# SCH_YY.net
KiCad netlist of a schematic drawn in EasyEDA
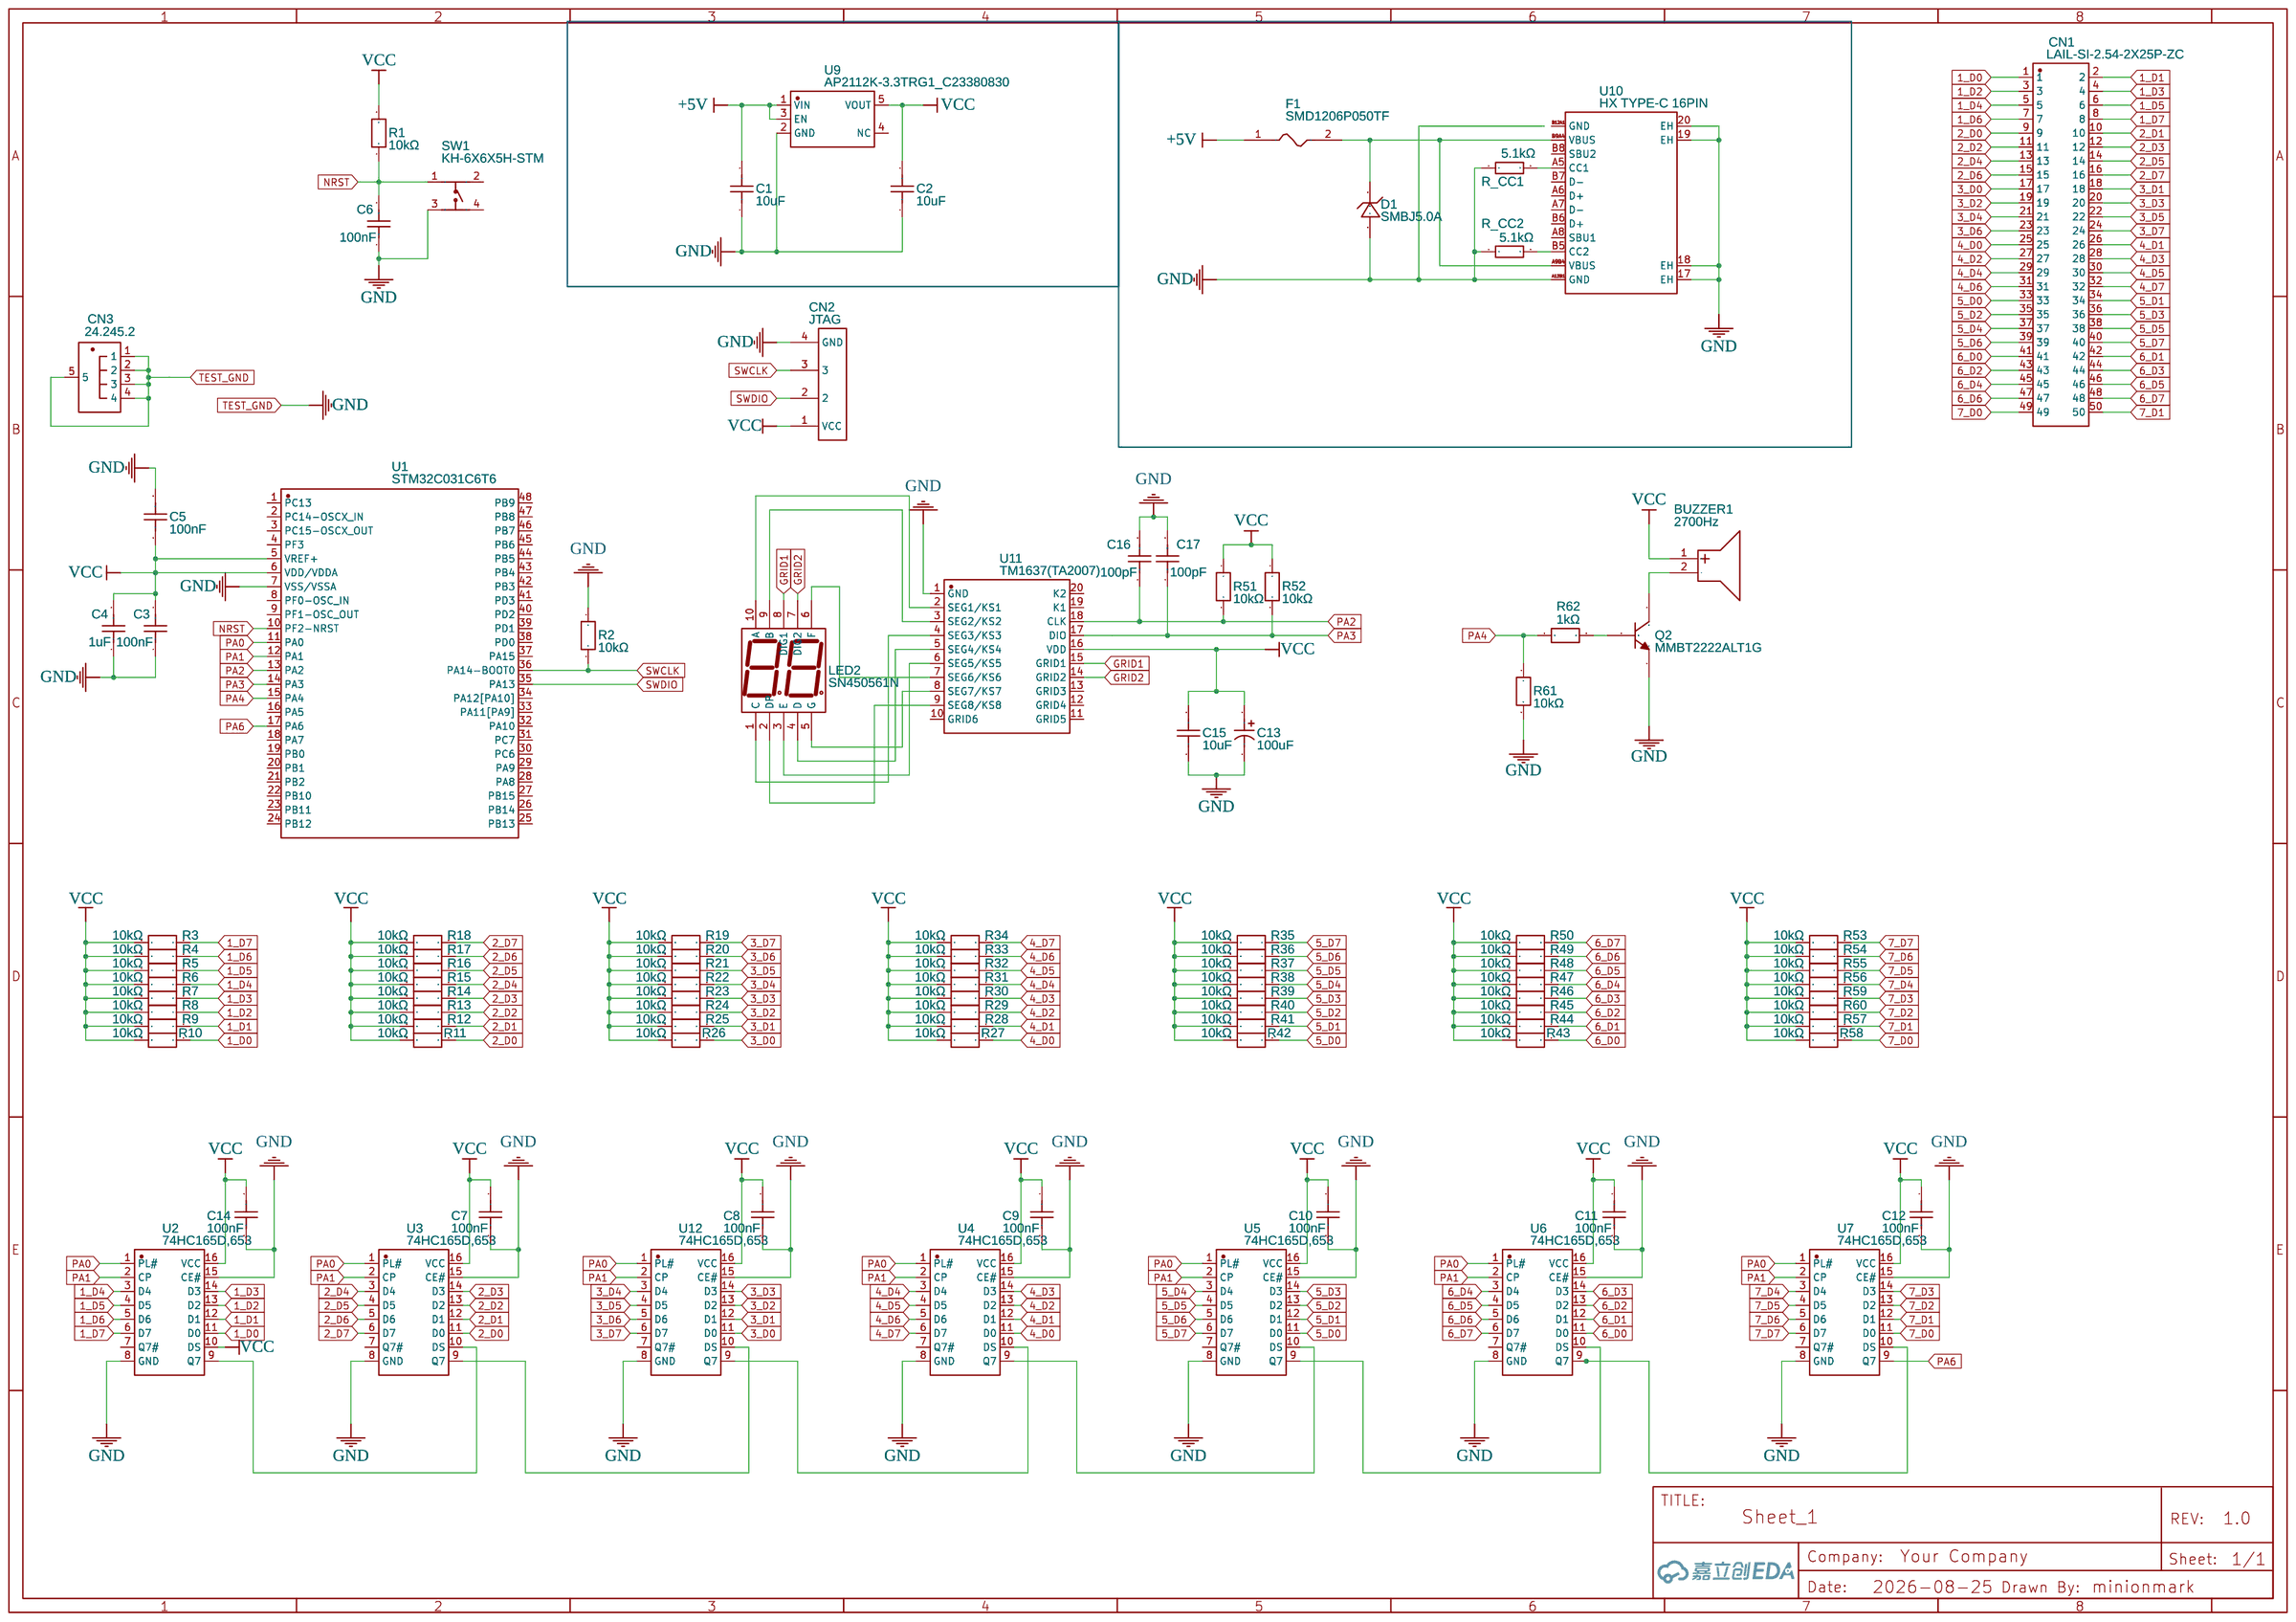
[diagram p0: schematic sheet]

(export (version "E")
  (design (tool "Eeschema 10.0.6"))
  (components
    (comp (ref "BUZZER1")
      (value "2700Hz")
      (fields
        (field (name "Manufacturer Part") "GSD9605YB-3V2800")
        (field (name "Manufacturer") "INGHAi(赢海)")
      )
      (libsource (lib "") (part "GSD9605YB-3V2800"))
    )
    (comp (ref "C1")
      (value "10uF")
      (fields
        (field (name "Manufacturer Part") "FCC0603X106K100CT")
        (field (name "Manufacturer") "FOJAN(富捷)")
      )
      (libsource (lib "") (part "FCC0603X106K100CT"))
    )
    (comp (ref "C2")
      (value "10uF")
      (fields
        (field (name "Manufacturer Part") "FCC0603X106K100CT")
        (field (name "Manufacturer") "FOJAN(富捷)")
      )
      (libsource (lib "") (part "FCC0603X106K100CT"))
    )
    (comp (ref "C3")
      (value "100nF")
      (fields (field (name "Manufacturer Part") "0603ZD104KAT2A") (field (name "Manufacturer") "Kyocera AVX"))
      (libsource (lib "") (part "0603ZD104KAT2A"))
    )
    (comp (ref "C4")
      (value "1uF")
      (fields (field (name "Manufacturer Part") "0603X105K100NT") (field (name "Manufacturer") "FH(风华)"))
      (libsource (lib "") (part "0603X105K100NT"))
    )
    (comp (ref "C5")
      (value "100nF")
      (fields (field (name "Manufacturer Part") "0603ZD104KAT2A") (field (name "Manufacturer") "Kyocera AVX"))
      (libsource (lib "") (part "0603ZD104KAT2A"))
    )
    (comp (ref "C6")
      (value "100nF")
      (fields (field (name "Manufacturer Part") "0603ZD104KAT2A") (field (name "Manufacturer") "Kyocera AVX"))
      (libsource (lib "") (part "0603ZD104KAT2A"))
    )
    (comp (ref "C7")
      (value "100nF")
      (fields (field (name "Manufacturer Part") "0603ZD104KAT2A") (field (name "Manufacturer") "Kyocera AVX"))
      (libsource (lib "") (part "0603ZD104KAT2A_1"))
    )
    (comp (ref "C8")
      (value "100nF")
      (fields (field (name "Manufacturer Part") "0603ZD104KAT2A") (field (name "Manufacturer") "Kyocera AVX"))
      (libsource (lib "") (part "0603ZD104KAT2A_1"))
    )
    (comp (ref "C9")
      (value "100nF")
      (fields (field (name "Manufacturer Part") "0603ZD104KAT2A") (field (name "Manufacturer") "Kyocera AVX"))
      (libsource (lib "") (part "0603ZD104KAT2A_1"))
    )
    (comp (ref "C10")
      (value "100nF")
      (fields (field (name "Manufacturer Part") "0603ZD104KAT2A") (field (name "Manufacturer") "Kyocera AVX"))
      (libsource (lib "") (part "0603ZD104KAT2A_1"))
    )
    (comp (ref "C11")
      (value "100nF")
      (fields (field (name "Manufacturer Part") "0603ZD104KAT2A") (field (name "Manufacturer") "Kyocera AVX"))
      (libsource (lib "") (part "0603ZD104KAT2A_1"))
    )
    (comp (ref "C12")
      (value "100nF")
      (fields (field (name "Manufacturer Part") "0603ZD104KAT2A") (field (name "Manufacturer") "Kyocera AVX"))
      (libsource (lib "") (part "0603ZD104KAT2A_1"))
    )
    (comp (ref "C13")
      (value "100uF")
      (fields (field (name "Manufacturer Part") "JVJ25V100M6x5") (field (name "Manufacturer") "JIERR(捷而瑞)"))
      (libsource (lib "") (part "JVJ25V100M6X5"))
    )
    (comp (ref "C14")
      (value "100nF")
      (fields (field (name "Manufacturer Part") "0603ZD104KAT2A") (field (name "Manufacturer") "Kyocera AVX"))
      (libsource (lib "") (part "0603ZD104KAT2A_1"))
    )
    (comp (ref "C15")
      (value "10uF")
      (fields
        (field (name "Manufacturer Part") "FCC0603X106K100CT")
        (field (name "Manufacturer") "FOJAN(富捷)")
      )
      (libsource (lib "") (part "FCC0603X106K100CT"))
    )
    (comp (ref "C16")
      (value "100pF")
      (fields
        (field (name "Manufacturer Part") "CC0603JRNPO9BN101")
        (field (name "Manufacturer") "YAGEO(国巨)")
      )
      (libsource (lib "") (part "CC0603JRNPO9BN101"))
    )
    (comp (ref "C17")
      (value "100pF")
      (fields
        (field (name "Manufacturer Part") "CC0603JRNPO9BN101")
        (field (name "Manufacturer") "YAGEO(国巨)")
      )
      (libsource (lib "") (part "CC0603JRNPO9BN101"))
    )
    (comp (ref "CN1")
      (value "LAIL-SI-2.54-2X25P-ZC")
      (fields (field (name "Manufacturer") "莱联"))
      (libsource (lib "") (part "LAIL-SI-2.54-2X25P-ZC"))
    )
    (comp (ref "CN2") (value "JTAG") (libsource (lib "") (part "JTAG")))
    (comp (ref "CN3")
      (value "24.245.2")
      (fields (field (name "Manufacturer") "AMASS(艾迈斯)"))
      (libsource (lib "") (part "24.245.2"))
    )
    (comp (ref "D1")
      (value "SMBJ5.0A")
      (fields (field (name "Manufacturer") "MDD(辰达半导体)"))
      (libsource (lib "") (part "SMBJ5.0A-C113974"))
    )
    (comp (ref "F1")
      (value "SMD1206P050TF")
      (fields (field (name "Manufacturer") "RUILON(瑞隆源)"))
      (libsource (lib "") (part "SMD1206P050TF"))
    )
    (comp (ref "LED2")
      (value "SN450561N")
      (fields (field (name "Manufacturer") "ARKLED(方舟)"))
      (libsource (lib "") (part "SN450561N"))
    )
    (comp (ref "Q2")
      (value "MMBT2222ALT1G")
      (fields (field (name "Manufacturer") "onsemi(安森美)"))
      (libsource (lib "") (part "MMBT2222ALT1G"))
    )
    (comp (ref "R1")
      (value "10kΩ")
      (fields (field (name "Manufacturer Part") "FRC0603J103 TS") (field (name "Manufacturer") "FOJAN(富捷)"))
      (libsource (lib "") (part "FRC0603J103TS_2"))
    )
    (comp (ref "R2")
      (value "10kΩ")
      (fields (field (name "Manufacturer Part") "FRC0603J103 TS") (field (name "Manufacturer") "FOJAN(富捷)"))
      (libsource (lib "") (part "FRC0603J103TS_1"))
    )
    (comp (ref "R3")
      (value "10kΩ")
      (fields (field (name "Manufacturer Part") "FRC0603J103 TS") (field (name "Manufacturer") "FOJAN(富捷)"))
      (libsource (lib "") (part "FRC0603J103TS"))
    )
    (comp (ref "R4")
      (value "10kΩ")
      (fields (field (name "Manufacturer Part") "FRC0603J103 TS") (field (name "Manufacturer") "FOJAN(富捷)"))
      (libsource (lib "") (part "FRC0603J103TS"))
    )
    (comp (ref "R5")
      (value "10kΩ")
      (fields (field (name "Manufacturer Part") "FRC0603J103 TS") (field (name "Manufacturer") "FOJAN(富捷)"))
      (libsource (lib "") (part "FRC0603J103TS"))
    )
    (comp (ref "R6")
      (value "10kΩ")
      (fields (field (name "Manufacturer Part") "FRC0603J103 TS") (field (name "Manufacturer") "FOJAN(富捷)"))
      (libsource (lib "") (part "FRC0603J103TS"))
    )
    (comp (ref "R7")
      (value "10kΩ")
      (fields (field (name "Manufacturer Part") "FRC0603J103 TS") (field (name "Manufacturer") "FOJAN(富捷)"))
      (libsource (lib "") (part "FRC0603J103TS"))
    )
    (comp (ref "R8")
      (value "10kΩ")
      (fields (field (name "Manufacturer Part") "FRC0603J103 TS") (field (name "Manufacturer") "FOJAN(富捷)"))
      (libsource (lib "") (part "FRC0603J103TS"))
    )
    (comp (ref "R9")
      (value "10kΩ")
      (fields (field (name "Manufacturer Part") "FRC0603J103 TS") (field (name "Manufacturer") "FOJAN(富捷)"))
      (libsource (lib "") (part "FRC0603J103TS"))
    )
    (comp (ref "R10")
      (value "10kΩ")
      (fields (field (name "Manufacturer Part") "FRC0603J103 TS") (field (name "Manufacturer") "FOJAN(富捷)"))
      (libsource (lib "") (part "FRC0603J103TS"))
    )
    (comp (ref "R11")
      (value "10kΩ")
      (fields (field (name "Manufacturer Part") "FRC0603J103 TS") (field (name "Manufacturer") "FOJAN(富捷)"))
      (libsource (lib "") (part "FRC0603J103TS"))
    )
    (comp (ref "R12")
      (value "10kΩ")
      (fields (field (name "Manufacturer Part") "FRC0603J103 TS") (field (name "Manufacturer") "FOJAN(富捷)"))
      (libsource (lib "") (part "FRC0603J103TS"))
    )
    (comp (ref "R13")
      (value "10kΩ")
      (fields (field (name "Manufacturer Part") "FRC0603J103 TS") (field (name "Manufacturer") "FOJAN(富捷)"))
      (libsource (lib "") (part "FRC0603J103TS"))
    )
    (comp (ref "R14")
      (value "10kΩ")
      (fields (field (name "Manufacturer Part") "FRC0603J103 TS") (field (name "Manufacturer") "FOJAN(富捷)"))
      (libsource (lib "") (part "FRC0603J103TS"))
    )
    (comp (ref "R15")
      (value "10kΩ")
      (fields (field (name "Manufacturer Part") "FRC0603J103 TS") (field (name "Manufacturer") "FOJAN(富捷)"))
      (libsource (lib "") (part "FRC0603J103TS"))
    )
    (comp (ref "R16")
      (value "10kΩ")
      (fields (field (name "Manufacturer Part") "FRC0603J103 TS") (field (name "Manufacturer") "FOJAN(富捷)"))
      (libsource (lib "") (part "FRC0603J103TS"))
    )
    (comp (ref "R17")
      (value "10kΩ")
      (fields (field (name "Manufacturer Part") "FRC0603J103 TS") (field (name "Manufacturer") "FOJAN(富捷)"))
      (libsource (lib "") (part "FRC0603J103TS"))
    )
    (comp (ref "R18")
      (value "10kΩ")
      (fields (field (name "Manufacturer Part") "FRC0603J103 TS") (field (name "Manufacturer") "FOJAN(富捷)"))
      (libsource (lib "") (part "FRC0603J103TS"))
    )
    (comp (ref "R19")
      (value "10kΩ")
      (fields (field (name "Manufacturer Part") "FRC0603J103 TS") (field (name "Manufacturer") "FOJAN(富捷)"))
      (libsource (lib "") (part "FRC0603J103TS"))
    )
    (comp (ref "R20")
      (value "10kΩ")
      (fields (field (name "Manufacturer Part") "FRC0603J103 TS") (field (name "Manufacturer") "FOJAN(富捷)"))
      (libsource (lib "") (part "FRC0603J103TS"))
    )
    (comp (ref "R21")
      (value "10kΩ")
      (fields (field (name "Manufacturer Part") "FRC0603J103 TS") (field (name "Manufacturer") "FOJAN(富捷)"))
      (libsource (lib "") (part "FRC0603J103TS"))
    )
    (comp (ref "R22")
      (value "10kΩ")
      (fields (field (name "Manufacturer Part") "FRC0603J103 TS") (field (name "Manufacturer") "FOJAN(富捷)"))
      (libsource (lib "") (part "FRC0603J103TS"))
    )
    (comp (ref "R23")
      (value "10kΩ")
      (fields (field (name "Manufacturer Part") "FRC0603J103 TS") (field (name "Manufacturer") "FOJAN(富捷)"))
      (libsource (lib "") (part "FRC0603J103TS"))
    )
    (comp (ref "R24")
      (value "10kΩ")
      (fields (field (name "Manufacturer Part") "FRC0603J103 TS") (field (name "Manufacturer") "FOJAN(富捷)"))
      (libsource (lib "") (part "FRC0603J103TS"))
    )
    (comp (ref "R25")
      (value "10kΩ")
      (fields (field (name "Manufacturer Part") "FRC0603J103 TS") (field (name "Manufacturer") "FOJAN(富捷)"))
      (libsource (lib "") (part "FRC0603J103TS"))
    )
    (comp (ref "R26")
      (value "10kΩ")
      (fields (field (name "Manufacturer Part") "FRC0603J103 TS") (field (name "Manufacturer") "FOJAN(富捷)"))
      (libsource (lib "") (part "FRC0603J103TS"))
    )
    (comp (ref "R27")
      (value "10kΩ")
      (fields (field (name "Manufacturer Part") "FRC0603J103 TS") (field (name "Manufacturer") "FOJAN(富捷)"))
      (libsource (lib "") (part "FRC0603J103TS"))
    )
    (comp (ref "R28")
      (value "10kΩ")
      (fields (field (name "Manufacturer Part") "FRC0603J103 TS") (field (name "Manufacturer") "FOJAN(富捷)"))
      (libsource (lib "") (part "FRC0603J103TS"))
    )
    (comp (ref "R29")
      (value "10kΩ")
      (fields (field (name "Manufacturer Part") "FRC0603J103 TS") (field (name "Manufacturer") "FOJAN(富捷)"))
      (libsource (lib "") (part "FRC0603J103TS"))
    )
    (comp (ref "R30")
      (value "10kΩ")
      (fields (field (name "Manufacturer Part") "FRC0603J103 TS") (field (name "Manufacturer") "FOJAN(富捷)"))
      (libsource (lib "") (part "FRC0603J103TS"))
    )
    (comp (ref "R31")
      (value "10kΩ")
      (fields (field (name "Manufacturer Part") "FRC0603J103 TS") (field (name "Manufacturer") "FOJAN(富捷)"))
      (libsource (lib "") (part "FRC0603J103TS"))
    )
    (comp (ref "R32")
      (value "10kΩ")
      (fields (field (name "Manufacturer Part") "FRC0603J103 TS") (field (name "Manufacturer") "FOJAN(富捷)"))
      (libsource (lib "") (part "FRC0603J103TS"))
    )
    (comp (ref "R33")
      (value "10kΩ")
      (fields (field (name "Manufacturer Part") "FRC0603J103 TS") (field (name "Manufacturer") "FOJAN(富捷)"))
      (libsource (lib "") (part "FRC0603J103TS"))
    )
    (comp (ref "R34")
      (value "10kΩ")
      (fields (field (name "Manufacturer Part") "FRC0603J103 TS") (field (name "Manufacturer") "FOJAN(富捷)"))
      (libsource (lib "") (part "FRC0603J103TS"))
    )
    (comp (ref "R35")
      (value "10kΩ")
      (fields (field (name "Manufacturer Part") "FRC0603J103 TS") (field (name "Manufacturer") "FOJAN(富捷)"))
      (libsource (lib "") (part "FRC0603J103TS"))
    )
    (comp (ref "R36")
      (value "10kΩ")
      (fields (field (name "Manufacturer Part") "FRC0603J103 TS") (field (name "Manufacturer") "FOJAN(富捷)"))
      (libsource (lib "") (part "FRC0603J103TS"))
    )
    (comp (ref "R37")
      (value "10kΩ")
      (fields (field (name "Manufacturer Part") "FRC0603J103 TS") (field (name "Manufacturer") "FOJAN(富捷)"))
      (libsource (lib "") (part "FRC0603J103TS"))
    )
    (comp (ref "R38")
      (value "10kΩ")
      (fields (field (name "Manufacturer Part") "FRC0603J103 TS") (field (name "Manufacturer") "FOJAN(富捷)"))
      (libsource (lib "") (part "FRC0603J103TS"))
    )
    (comp (ref "R39")
      (value "10kΩ")
      (fields (field (name "Manufacturer Part") "FRC0603J103 TS") (field (name "Manufacturer") "FOJAN(富捷)"))
      (libsource (lib "") (part "FRC0603J103TS"))
    )
    (comp (ref "R40")
      (value "10kΩ")
      (fields (field (name "Manufacturer Part") "FRC0603J103 TS") (field (name "Manufacturer") "FOJAN(富捷)"))
      (libsource (lib "") (part "FRC0603J103TS"))
    )
    (comp (ref "R41")
      (value "10kΩ")
      (fields (field (name "Manufacturer Part") "FRC0603J103 TS") (field (name "Manufacturer") "FOJAN(富捷)"))
      (libsource (lib "") (part "FRC0603J103TS"))
    )
    (comp (ref "R42")
      (value "10kΩ")
      (fields (field (name "Manufacturer Part") "FRC0603J103 TS") (field (name "Manufacturer") "FOJAN(富捷)"))
      (libsource (lib "") (part "FRC0603J103TS"))
    )
    (comp (ref "R43")
      (value "10kΩ")
      (fields (field (name "Manufacturer Part") "FRC0603J103 TS") (field (name "Manufacturer") "FOJAN(富捷)"))
      (libsource (lib "") (part "FRC0603J103TS"))
    )
    (comp (ref "R44")
      (value "10kΩ")
      (fields (field (name "Manufacturer Part") "FRC0603J103 TS") (field (name "Manufacturer") "FOJAN(富捷)"))
      (libsource (lib "") (part "FRC0603J103TS"))
    )
    (comp (ref "R45")
      (value "10kΩ")
      (fields (field (name "Manufacturer Part") "FRC0603J103 TS") (field (name "Manufacturer") "FOJAN(富捷)"))
      (libsource (lib "") (part "FRC0603J103TS"))
    )
    (comp (ref "R46")
      (value "10kΩ")
      (fields (field (name "Manufacturer Part") "FRC0603J103 TS") (field (name "Manufacturer") "FOJAN(富捷)"))
      (libsource (lib "") (part "FRC0603J103TS"))
    )
    (comp (ref "R47")
      (value "10kΩ")
      (fields (field (name "Manufacturer Part") "FRC0603J103 TS") (field (name "Manufacturer") "FOJAN(富捷)"))
      (libsource (lib "") (part "FRC0603J103TS"))
    )
    (comp (ref "R48")
      (value "10kΩ")
      (fields (field (name "Manufacturer Part") "FRC0603J103 TS") (field (name "Manufacturer") "FOJAN(富捷)"))
      (libsource (lib "") (part "FRC0603J103TS"))
    )
    (comp (ref "R49")
      (value "10kΩ")
      (fields (field (name "Manufacturer Part") "FRC0603J103 TS") (field (name "Manufacturer") "FOJAN(富捷)"))
      (libsource (lib "") (part "FRC0603J103TS"))
    )
    (comp (ref "R50")
      (value "10kΩ")
      (fields (field (name "Manufacturer Part") "FRC0603J103 TS") (field (name "Manufacturer") "FOJAN(富捷)"))
      (libsource (lib "") (part "FRC0603J103TS"))
    )
    (comp (ref "R51")
      (value "10kΩ")
      (fields (field (name "Manufacturer Part") "FRC0603J103 TS") (field (name "Manufacturer") "FOJAN(富捷)"))
      (libsource (lib "") (part "FRC0603J103TS_1"))
    )
    (comp (ref "R52")
      (value "10kΩ")
      (fields (field (name "Manufacturer Part") "FRC0603J103 TS") (field (name "Manufacturer") "FOJAN(富捷)"))
      (libsource (lib "") (part "FRC0603J103TS_1"))
    )
    (comp (ref "R53")
      (value "10kΩ")
      (fields (field (name "Manufacturer Part") "FRC0603J103 TS") (field (name "Manufacturer") "FOJAN(富捷)"))
      (libsource (lib "") (part "FRC0603J103TS"))
    )
    (comp (ref "R54")
      (value "10kΩ")
      (fields (field (name "Manufacturer Part") "FRC0603J103 TS") (field (name "Manufacturer") "FOJAN(富捷)"))
      (libsource (lib "") (part "FRC0603J103TS"))
    )
    (comp (ref "R55")
      (value "10kΩ")
      (fields (field (name "Manufacturer Part") "FRC0603J103 TS") (field (name "Manufacturer") "FOJAN(富捷)"))
      (libsource (lib "") (part "FRC0603J103TS"))
    )
    (comp (ref "R56")
      (value "10kΩ")
      (fields (field (name "Manufacturer Part") "FRC0603J103 TS") (field (name "Manufacturer") "FOJAN(富捷)"))
      (libsource (lib "") (part "FRC0603J103TS"))
    )
    (comp (ref "R57")
      (value "10kΩ")
      (fields (field (name "Manufacturer Part") "FRC0603J103 TS") (field (name "Manufacturer") "FOJAN(富捷)"))
      (libsource (lib "") (part "FRC0603J103TS"))
    )
    (comp (ref "R58")
      (value "10kΩ")
      (fields (field (name "Manufacturer Part") "FRC0603J103 TS") (field (name "Manufacturer") "FOJAN(富捷)"))
      (libsource (lib "") (part "FRC0603J103TS"))
    )
    (comp (ref "R59")
      (value "10kΩ")
      (fields (field (name "Manufacturer Part") "FRC0603J103 TS") (field (name "Manufacturer") "FOJAN(富捷)"))
      (libsource (lib "") (part "FRC0603J103TS"))
    )
    (comp (ref "R60")
      (value "10kΩ")
      (fields (field (name "Manufacturer Part") "FRC0603J103 TS") (field (name "Manufacturer") "FOJAN(富捷)"))
      (libsource (lib "") (part "FRC0603J103TS"))
    )
    (comp (ref "R61")
      (value "10kΩ")
      (fields (field (name "Manufacturer Part") "FRC0603J103 TS") (field (name "Manufacturer") "FOJAN(富捷)"))
      (libsource (lib "") (part "FRC0603J103TS_1"))
    )
    (comp (ref "R62")
      (value "1kΩ")
      (fields (field (name "Manufacturer Part") "FRC0603F1001TS") (field (name "Manufacturer") "FOJAN(富捷)"))
      (libsource (lib "") (part "FRC0603F1001TS"))
    )
    (comp (ref "R_CC1")
      (value "5.1kΩ")
      (fields (field (name "Manufacturer Part") "RT0603BRD075K1L") (field (name "Manufacturer") "YAGEO(国巨)"))
      (libsource (lib "") (part "RT0603BRD075K1L"))
    )
    (comp (ref "R_CC2")
      (value "5.1kΩ")
      (fields (field (name "Manufacturer Part") "RT0603BRD075K1L") (field (name "Manufacturer") "YAGEO(国巨)"))
      (libsource (lib "") (part "RT0603BRD075K1L"))
    )
    (comp (ref "SW1")
      (value "KH-6X6X5H-STM")
      (fields (field (name "Manufacturer") "kinghelm(金航标)"))
      (libsource (lib "") (part "KH-6X6X5H-STM"))
    )
    (comp (ref "U1")
      (value "STM32C031C6T6")
      (fields (field (name "Manufacturer") "ST(意法半导体)"))
      (libsource (lib "") (part "STM32C031C6T6"))
    )
    (comp (ref "U2")
      (value "74HC165D,653")
      (fields (field (name "Manufacturer") "Nexperia(安世)"))
      (libsource (lib "") (part "74HC165D,653"))
    )
    (comp (ref "U3")
      (value "74HC165D,653")
      (fields (field (name "Manufacturer") "Nexperia(安世)"))
      (libsource (lib "") (part "74HC165D,653"))
    )
    (comp (ref "U4")
      (value "74HC165D,653")
      (fields (field (name "Manufacturer") "Nexperia(安世)"))
      (libsource (lib "") (part "74HC165D,653"))
    )
    (comp (ref "U5")
      (value "74HC165D,653")
      (fields (field (name "Manufacturer") "Nexperia(安世)"))
      (libsource (lib "") (part "74HC165D,653"))
    )
    (comp (ref "U6")
      (value "74HC165D,653")
      (fields (field (name "Manufacturer") "Nexperia(安世)"))
      (libsource (lib "") (part "74HC165D,653"))
    )
    (comp (ref "U7")
      (value "74HC165D,653")
      (fields (field (name "Manufacturer") "Nexperia(安世)"))
      (libsource (lib "") (part "74HC165D,653"))
    )
    (comp (ref "U9")
      (value "AP2112K-3.3TRG1_C23380830")
      (fields
        (field (name "Manufacturer Part") "AP2112K-3.3TRG1")
        (field (name "Manufacturer") "TECH PUBLIC(台舟)")
      )
      (libsource (lib "") (part "AP2112K-3.3TRG1_C23380830"))
    )
    (comp (ref "U10")
      (value "HX TYPE-C 16PIN")
      (fields (field (name "Manufacturer") "hanxia(韩下)"))
      (libsource (lib "") (part "HX TYPE-C 16PIN"))
    )
    (comp (ref "U11")
      (value "TM1637(TA2007)")
      (fields (field (name "Manufacturer") "TM(天微)"))
      (libsource (lib "") (part "TM1637(TA2007)"))
    )
    (comp (ref "U12")
      (value "74HC165D,653")
      (fields (field (name "Manufacturer") "Nexperia(安世)"))
      (libsource (lib "") (part "74HC165D,653"))
    )
  )
  (nets
    (net (code "1") (name "+5V") (class "Default")
      (node (ref "C1") (pin "2") (pinfunction "2_2") (pintype "unspecified"))
      (node (ref "F1") (pin "1") (pinfunction "1_1") (pintype "unspecified"))
      (node (ref "U9") (pin "1") (pinfunction "VIN_1") (pintype "unspecified"))
      (node (ref "U9") (pin "3") (pinfunction "EN_3") (pintype "unspecified"))
    )
    (net (code "2") (name "1_D0") (class "Default")
      (node (ref "CN1") (pin "1") (pinfunction "1_1") (pintype "unspecified"))
      (node (ref "R10") (pin "1") (pinfunction "1_1") (pintype "unspecified"))
      (node (ref "U2") (pin "11") (pinfunction "D0_11") (pintype "unspecified"))
    )
    (net (code "3") (name "1_D1") (class "Default")
      (node (ref "CN1") (pin "2") (pinfunction "2_2") (pintype "unspecified"))
      (node (ref "R9") (pin "1") (pinfunction "1_1") (pintype "unspecified"))
      (node (ref "U2") (pin "12") (pinfunction "D1_12") (pintype "unspecified"))
    )
    (net (code "4") (name "1_D2") (class "Default")
      (node (ref "CN1") (pin "3") (pinfunction "3_3") (pintype "unspecified"))
      (node (ref "R8") (pin "1") (pinfunction "1_1") (pintype "unspecified"))
      (node (ref "U2") (pin "13") (pinfunction "D2_13") (pintype "unspecified"))
    )
    (net (code "5") (name "1_D3") (class "Default")
      (node (ref "CN1") (pin "4") (pinfunction "4_4") (pintype "unspecified"))
      (node (ref "R7") (pin "1") (pinfunction "1_1") (pintype "unspecified"))
      (node (ref "U2") (pin "14") (pinfunction "D3_14") (pintype "unspecified"))
    )
    (net (code "6") (name "1_D4") (class "Default")
      (node (ref "CN1") (pin "5") (pinfunction "5_5") (pintype "unspecified"))
      (node (ref "R6") (pin "1") (pinfunction "1_1") (pintype "unspecified"))
      (node (ref "U2") (pin "3") (pinfunction "D4_3") (pintype "unspecified"))
    )
    (net (code "7") (name "1_D5") (class "Default")
      (node (ref "CN1") (pin "6") (pinfunction "6_6") (pintype "unspecified"))
      (node (ref "R5") (pin "1") (pinfunction "1_1") (pintype "unspecified"))
      (node (ref "U2") (pin "4") (pinfunction "D5_4") (pintype "unspecified"))
    )
    (net (code "8") (name "1_D6") (class "Default")
      (node (ref "CN1") (pin "7") (pinfunction "7_7") (pintype "unspecified"))
      (node (ref "R4") (pin "1") (pinfunction "1_1") (pintype "unspecified"))
      (node (ref "U2") (pin "5") (pinfunction "D6_5") (pintype "unspecified"))
    )
    (net (code "9") (name "1_D7") (class "Default")
      (node (ref "CN1") (pin "8") (pinfunction "8_8") (pintype "unspecified"))
      (node (ref "R3") (pin "1") (pinfunction "1_1") (pintype "unspecified"))
      (node (ref "U2") (pin "6") (pinfunction "D7_6") (pintype "unspecified"))
    )
    (net (code "10") (name "2_D0") (class "Default")
      (node (ref "CN1") (pin "9") (pinfunction "9_9") (pintype "unspecified"))
      (node (ref "R11") (pin "1") (pinfunction "1_1") (pintype "unspecified"))
      (node (ref "U3") (pin "11") (pinfunction "D0_11") (pintype "unspecified"))
    )
    (net (code "11") (name "2_D1") (class "Default")
      (node (ref "CN1") (pin "10") (pinfunction "10_10") (pintype "unspecified"))
      (node (ref "R12") (pin "1") (pinfunction "1_1") (pintype "unspecified"))
      (node (ref "U3") (pin "12") (pinfunction "D1_12") (pintype "unspecified"))
    )
    (net (code "12") (name "2_D2") (class "Default")
      (node (ref "CN1") (pin "11") (pinfunction "11_11") (pintype "unspecified"))
      (node (ref "R13") (pin "1") (pinfunction "1_1") (pintype "unspecified"))
      (node (ref "U3") (pin "13") (pinfunction "D2_13") (pintype "unspecified"))
    )
    (net (code "13") (name "2_D3") (class "Default")
      (node (ref "CN1") (pin "12") (pinfunction "12_12") (pintype "unspecified"))
      (node (ref "R14") (pin "1") (pinfunction "1_1") (pintype "unspecified"))
      (node (ref "U3") (pin "14") (pinfunction "D3_14") (pintype "unspecified"))
    )
    (net (code "14") (name "2_D4") (class "Default")
      (node (ref "CN1") (pin "13") (pinfunction "13_13") (pintype "unspecified"))
      (node (ref "R15") (pin "1") (pinfunction "1_1") (pintype "unspecified"))
      (node (ref "U3") (pin "3") (pinfunction "D4_3") (pintype "unspecified"))
    )
    (net (code "15") (name "2_D5") (class "Default")
      (node (ref "CN1") (pin "14") (pinfunction "14_14") (pintype "unspecified"))
      (node (ref "R16") (pin "1") (pinfunction "1_1") (pintype "unspecified"))
      (node (ref "U3") (pin "4") (pinfunction "D5_4") (pintype "unspecified"))
    )
    (net (code "16") (name "2_D6") (class "Default")
      (node (ref "CN1") (pin "15") (pinfunction "15_15") (pintype "unspecified"))
      (node (ref "R17") (pin "1") (pinfunction "1_1") (pintype "unspecified"))
      (node (ref "U3") (pin "5") (pinfunction "D6_5") (pintype "unspecified"))
    )
    (net (code "17") (name "2_D7") (class "Default")
      (node (ref "CN1") (pin "16") (pinfunction "16_16") (pintype "unspecified"))
      (node (ref "R18") (pin "1") (pinfunction "1_1") (pintype "unspecified"))
      (node (ref "U3") (pin "6") (pinfunction "D7_6") (pintype "unspecified"))
    )
    (net (code "18") (name "3_D0") (class "Default")
      (node (ref "CN1") (pin "17") (pinfunction "17_17") (pintype "unspecified"))
      (node (ref "R26") (pin "1") (pinfunction "1_1") (pintype "unspecified"))
      (node (ref "U12") (pin "11") (pinfunction "D0_11") (pintype "unspecified"))
    )
    (net (code "19") (name "3_D1") (class "Default")
      (node (ref "CN1") (pin "18") (pinfunction "18_18") (pintype "unspecified"))
      (node (ref "R25") (pin "1") (pinfunction "1_1") (pintype "unspecified"))
      (node (ref "U12") (pin "12") (pinfunction "D1_12") (pintype "unspecified"))
    )
    (net (code "20") (name "3_D2") (class "Default")
      (node (ref "CN1") (pin "19") (pinfunction "19_19") (pintype "unspecified"))
      (node (ref "R24") (pin "1") (pinfunction "1_1") (pintype "unspecified"))
      (node (ref "U12") (pin "13") (pinfunction "D2_13") (pintype "unspecified"))
    )
    (net (code "21") (name "3_D3") (class "Default")
      (node (ref "CN1") (pin "20") (pinfunction "20_20") (pintype "unspecified"))
      (node (ref "R23") (pin "1") (pinfunction "1_1") (pintype "unspecified"))
      (node (ref "U12") (pin "14") (pinfunction "D3_14") (pintype "unspecified"))
    )
    (net (code "22") (name "3_D4") (class "Default")
      (node (ref "CN1") (pin "21") (pinfunction "21_21") (pintype "unspecified"))
      (node (ref "R22") (pin "1") (pinfunction "1_1") (pintype "unspecified"))
      (node (ref "U12") (pin "3") (pinfunction "D4_3") (pintype "unspecified"))
    )
    (net (code "23") (name "3_D5") (class "Default")
      (node (ref "CN1") (pin "22") (pinfunction "22_22") (pintype "unspecified"))
      (node (ref "R21") (pin "1") (pinfunction "1_1") (pintype "unspecified"))
      (node (ref "U12") (pin "4") (pinfunction "D5_4") (pintype "unspecified"))
    )
    (net (code "24") (name "3_D6") (class "Default")
      (node (ref "CN1") (pin "23") (pinfunction "23_23") (pintype "unspecified"))
      (node (ref "R20") (pin "1") (pinfunction "1_1") (pintype "unspecified"))
      (node (ref "U12") (pin "5") (pinfunction "D6_5") (pintype "unspecified"))
    )
    (net (code "25") (name "3_D7") (class "Default")
      (node (ref "CN1") (pin "24") (pinfunction "24_24") (pintype "unspecified"))
      (node (ref "R19") (pin "1") (pinfunction "1_1") (pintype "unspecified"))
      (node (ref "U12") (pin "6") (pinfunction "D7_6") (pintype "unspecified"))
    )
    (net (code "26") (name "4_D0") (class "Default")
      (node (ref "CN1") (pin "25") (pinfunction "25_25") (pintype "unspecified"))
      (node (ref "R27") (pin "1") (pinfunction "1_1") (pintype "unspecified"))
      (node (ref "U4") (pin "11") (pinfunction "D0_11") (pintype "unspecified"))
    )
    (net (code "27") (name "4_D1") (class "Default")
      (node (ref "CN1") (pin "26") (pinfunction "26_26") (pintype "unspecified"))
      (node (ref "R28") (pin "1") (pinfunction "1_1") (pintype "unspecified"))
      (node (ref "U4") (pin "12") (pinfunction "D1_12") (pintype "unspecified"))
    )
    (net (code "28") (name "4_D2") (class "Default")
      (node (ref "CN1") (pin "27") (pinfunction "27_27") (pintype "unspecified"))
      (node (ref "R29") (pin "1") (pinfunction "1_1") (pintype "unspecified"))
      (node (ref "U4") (pin "13") (pinfunction "D2_13") (pintype "unspecified"))
    )
    (net (code "29") (name "4_D3") (class "Default")
      (node (ref "CN1") (pin "28") (pinfunction "28_28") (pintype "unspecified"))
      (node (ref "R30") (pin "1") (pinfunction "1_1") (pintype "unspecified"))
      (node (ref "U4") (pin "14") (pinfunction "D3_14") (pintype "unspecified"))
    )
    (net (code "30") (name "4_D4") (class "Default")
      (node (ref "CN1") (pin "29") (pinfunction "29_29") (pintype "unspecified"))
      (node (ref "R31") (pin "1") (pinfunction "1_1") (pintype "unspecified"))
      (node (ref "U4") (pin "3") (pinfunction "D4_3") (pintype "unspecified"))
    )
    (net (code "31") (name "4_D5") (class "Default")
      (node (ref "CN1") (pin "30") (pinfunction "30_30") (pintype "unspecified"))
      (node (ref "R32") (pin "1") (pinfunction "1_1") (pintype "unspecified"))
      (node (ref "U4") (pin "4") (pinfunction "D5_4") (pintype "unspecified"))
    )
    (net (code "32") (name "4_D6") (class "Default")
      (node (ref "CN1") (pin "31") (pinfunction "31_31") (pintype "unspecified"))
      (node (ref "R33") (pin "1") (pinfunction "1_1") (pintype "unspecified"))
      (node (ref "U4") (pin "5") (pinfunction "D6_5") (pintype "unspecified"))
    )
    (net (code "33") (name "4_D7") (class "Default")
      (node (ref "CN1") (pin "32") (pinfunction "32_32") (pintype "unspecified"))
      (node (ref "R34") (pin "1") (pinfunction "1_1") (pintype "unspecified"))
      (node (ref "U4") (pin "6") (pinfunction "D7_6") (pintype "unspecified"))
    )
    (net (code "34") (name "5_D0") (class "Default")
      (node (ref "CN1") (pin "33") (pinfunction "33_33") (pintype "unspecified"))
      (node (ref "R42") (pin "1") (pinfunction "1_1") (pintype "unspecified"))
      (node (ref "U5") (pin "11") (pinfunction "D0_11") (pintype "unspecified"))
    )
    (net (code "35") (name "5_D1") (class "Default")
      (node (ref "CN1") (pin "34") (pinfunction "34_34") (pintype "unspecified"))
      (node (ref "R41") (pin "1") (pinfunction "1_1") (pintype "unspecified"))
      (node (ref "U5") (pin "12") (pinfunction "D1_12") (pintype "unspecified"))
    )
    (net (code "36") (name "5_D2") (class "Default")
      (node (ref "CN1") (pin "35") (pinfunction "35_35") (pintype "unspecified"))
      (node (ref "R40") (pin "1") (pinfunction "1_1") (pintype "unspecified"))
      (node (ref "U5") (pin "13") (pinfunction "D2_13") (pintype "unspecified"))
    )
    (net (code "37") (name "5_D3") (class "Default")
      (node (ref "CN1") (pin "36") (pinfunction "36_36") (pintype "unspecified"))
      (node (ref "R39") (pin "1") (pinfunction "1_1") (pintype "unspecified"))
      (node (ref "U5") (pin "14") (pinfunction "D3_14") (pintype "unspecified"))
    )
    (net (code "38") (name "5_D4") (class "Default")
      (node (ref "CN1") (pin "37") (pinfunction "37_37") (pintype "unspecified"))
      (node (ref "R38") (pin "1") (pinfunction "1_1") (pintype "unspecified"))
      (node (ref "U5") (pin "3") (pinfunction "D4_3") (pintype "unspecified"))
    )
    (net (code "39") (name "5_D5") (class "Default")
      (node (ref "CN1") (pin "38") (pinfunction "38_38") (pintype "unspecified"))
      (node (ref "R37") (pin "1") (pinfunction "1_1") (pintype "unspecified"))
      (node (ref "U5") (pin "4") (pinfunction "D5_4") (pintype "unspecified"))
    )
    (net (code "40") (name "5_D6") (class "Default")
      (node (ref "CN1") (pin "39") (pinfunction "39_39") (pintype "unspecified"))
      (node (ref "R36") (pin "1") (pinfunction "1_1") (pintype "unspecified"))
      (node (ref "U5") (pin "5") (pinfunction "D6_5") (pintype "unspecified"))
    )
    (net (code "41") (name "5_D7") (class "Default")
      (node (ref "CN1") (pin "40") (pinfunction "40_40") (pintype "unspecified"))
      (node (ref "R35") (pin "1") (pinfunction "1_1") (pintype "unspecified"))
      (node (ref "U5") (pin "6") (pinfunction "D7_6") (pintype "unspecified"))
    )
    (net (code "42") (name "6_D0") (class "Default")
      (node (ref "CN1") (pin "41") (pinfunction "41_41") (pintype "unspecified"))
      (node (ref "R43") (pin "1") (pinfunction "1_1") (pintype "unspecified"))
      (node (ref "U6") (pin "11") (pinfunction "D0_11") (pintype "unspecified"))
    )
    (net (code "43") (name "6_D1") (class "Default")
      (node (ref "CN1") (pin "42") (pinfunction "42_42") (pintype "unspecified"))
      (node (ref "R44") (pin "1") (pinfunction "1_1") (pintype "unspecified"))
      (node (ref "U6") (pin "12") (pinfunction "D1_12") (pintype "unspecified"))
    )
    (net (code "44") (name "6_D2") (class "Default")
      (node (ref "CN1") (pin "43") (pinfunction "43_43") (pintype "unspecified"))
      (node (ref "R45") (pin "1") (pinfunction "1_1") (pintype "unspecified"))
      (node (ref "U6") (pin "13") (pinfunction "D2_13") (pintype "unspecified"))
    )
    (net (code "45") (name "6_D3") (class "Default")
      (node (ref "CN1") (pin "44") (pinfunction "44_44") (pintype "unspecified"))
      (node (ref "R46") (pin "1") (pinfunction "1_1") (pintype "unspecified"))
      (node (ref "U6") (pin "14") (pinfunction "D3_14") (pintype "unspecified"))
    )
    (net (code "46") (name "6_D4") (class "Default")
      (node (ref "CN1") (pin "45") (pinfunction "45_45") (pintype "unspecified"))
      (node (ref "R47") (pin "1") (pinfunction "1_1") (pintype "unspecified"))
      (node (ref "U6") (pin "3") (pinfunction "D4_3") (pintype "unspecified"))
    )
    (net (code "47") (name "6_D5") (class "Default")
      (node (ref "CN1") (pin "46") (pinfunction "46_46") (pintype "unspecified"))
      (node (ref "R48") (pin "1") (pinfunction "1_1") (pintype "unspecified"))
      (node (ref "U6") (pin "4") (pinfunction "D5_4") (pintype "unspecified"))
    )
    (net (code "48") (name "6_D6") (class "Default")
      (node (ref "CN1") (pin "47") (pinfunction "47_47") (pintype "unspecified"))
      (node (ref "R49") (pin "1") (pinfunction "1_1") (pintype "unspecified"))
      (node (ref "U6") (pin "5") (pinfunction "D6_5") (pintype "unspecified"))
    )
    (net (code "49") (name "6_D7") (class "Default")
      (node (ref "CN1") (pin "48") (pinfunction "48_48") (pintype "unspecified"))
      (node (ref "R50") (pin "1") (pinfunction "1_1") (pintype "unspecified"))
      (node (ref "U6") (pin "6") (pinfunction "D7_6") (pintype "unspecified"))
    )
    (net (code "50") (name "7_D0") (class "Default")
      (node (ref "CN1") (pin "49") (pinfunction "49_49") (pintype "unspecified"))
      (node (ref "R58") (pin "1") (pinfunction "1_1") (pintype "unspecified"))
      (node (ref "U7") (pin "11") (pinfunction "D0_11") (pintype "unspecified"))
    )
    (net (code "51") (name "7_D1") (class "Default")
      (node (ref "CN1") (pin "50") (pinfunction "50_50") (pintype "unspecified"))
      (node (ref "R57") (pin "1") (pinfunction "1_1") (pintype "unspecified"))
      (node (ref "U7") (pin "12") (pinfunction "D1_12") (pintype "unspecified"))
    )
    (net (code "52") (name "7_D2") (class "Default")
      (node (ref "R60") (pin "1") (pinfunction "1_1") (pintype "unspecified"))
      (node (ref "U7") (pin "13") (pinfunction "D2_13") (pintype "unspecified"))
    )
    (net (code "53") (name "7_D3") (class "Default")
      (node (ref "R59") (pin "1") (pinfunction "1_1") (pintype "unspecified"))
      (node (ref "U7") (pin "14") (pinfunction "D3_14") (pintype "unspecified"))
    )
    (net (code "54") (name "7_D4") (class "Default")
      (node (ref "R56") (pin "1") (pinfunction "1_1") (pintype "unspecified"))
      (node (ref "U7") (pin "3") (pinfunction "D4_3") (pintype "unspecified"))
    )
    (net (code "55") (name "7_D5") (class "Default")
      (node (ref "R55") (pin "1") (pinfunction "1_1") (pintype "unspecified"))
      (node (ref "U7") (pin "4") (pinfunction "D5_4") (pintype "unspecified"))
    )
    (net (code "56") (name "7_D6") (class "Default")
      (node (ref "R54") (pin "1") (pinfunction "1_1") (pintype "unspecified"))
      (node (ref "U7") (pin "5") (pinfunction "D6_5") (pintype "unspecified"))
    )
    (net (code "57") (name "7_D7") (class "Default")
      (node (ref "R53") (pin "1") (pinfunction "1_1") (pintype "unspecified"))
      (node (ref "U7") (pin "6") (pinfunction "D7_6") (pintype "unspecified"))
    )
    (net (code "58") (name "GRID1") (class "Default")
      (node (ref "LED2") (pin "8") (pinfunction "DIG1_8") (pintype "unspecified"))
      (node (ref "U11") (pin "15") (pinfunction "GRID1_15") (pintype "unspecified"))
    )
    (net (code "59") (name "GRID2") (class "Default")
      (node (ref "LED2") (pin "7") (pinfunction "DIG2_7") (pintype "unspecified"))
      (node (ref "U11") (pin "14") (pinfunction "GRID2_14") (pintype "unspecified"))
    )
    (net (code "60") (name "NRST") (class "Default")
      (node (ref "C6") (pin "2") (pinfunction "2_2") (pintype "unspecified"))
      (node (ref "R1") (pin "1") (pinfunction "1_1") (pintype "unspecified"))
      (node (ref "SW1") (pin "1") (pinfunction "1_1") (pintype "unspecified"))
      (node (ref "U1") (pin "10") (pinfunction "PF2-NRST_10") (pintype "unspecified"))
    )
    (net (code "61") (name "Net-(BUZZER1--)") (class "Default")
      (node (ref "BUZZER1") (pin "2") (pinfunction "-_2") (pintype "unspecified"))
      (node (ref "Q2") (pin "3") (pinfunction "C_3") (pintype "unspecified"))
    )
    (net (code "62") (name "Net-(D1-C)") (class "Default")
      (node (ref "D1") (pin "1") (pinfunction "C_1") (pintype "unspecified"))
      (node (ref "F1") (pin "2") (pinfunction "2_2") (pintype "unspecified"))
      (node (ref "U10") (pin "A9B4") (pinfunction "VBUS_A9B4") (pintype "unspecified"))
      (node (ref "U10") (pin "B9A4") (pinfunction "VBUS_B9A4") (pintype "unspecified"))
    )
    (net (code "63") (name "Net-(LED2-A)") (class "Default")
      (node (ref "LED2") (pin "10") (pinfunction "A_10") (pintype "unspecified"))
      (node (ref "U11") (pin "2") (pinfunction "SEG1/KS1_2") (pintype "unspecified"))
    )
    (net (code "64") (name "Net-(LED2-B)") (class "Default")
      (node (ref "LED2") (pin "9") (pinfunction "B_9") (pintype "unspecified"))
      (node (ref "U11") (pin "3") (pinfunction "SEG2/KS2_3") (pintype "unspecified"))
    )
    (net (code "65") (name "Net-(LED2-C)") (class "Default")
      (node (ref "LED2") (pin "1") (pinfunction "C_1") (pintype "unspecified"))
      (node (ref "U11") (pin "4") (pinfunction "SEG3/KS3_4") (pintype "unspecified"))
    )
    (net (code "66") (name "Net-(LED2-D)") (class "Default")
      (node (ref "LED2") (pin "4") (pinfunction "D_4") (pintype "unspecified"))
      (node (ref "U11") (pin "5") (pinfunction "SEG4/KS4_5") (pintype "unspecified"))
    )
    (net (code "67") (name "Net-(LED2-DP)") (class "Default")
      (node (ref "LED2") (pin "2") (pinfunction "DP_2") (pintype "unspecified"))
      (node (ref "U11") (pin "9") (pinfunction "SEG8/KS8_9") (pintype "unspecified"))
    )
    (net (code "68") (name "Net-(LED2-E)") (class "Default")
      (node (ref "LED2") (pin "3") (pinfunction "E_3") (pintype "unspecified"))
      (node (ref "U11") (pin "6") (pinfunction "SEG5/KS5_6") (pintype "unspecified"))
    )
    (net (code "69") (name "Net-(LED2-F)") (class "Default")
      (node (ref "LED2") (pin "6") (pinfunction "F_6") (pintype "unspecified"))
      (node (ref "U11") (pin "7") (pinfunction "SEG6/KS6_7") (pintype "unspecified"))
    )
    (net (code "70") (name "Net-(LED2-G)") (class "Default")
      (node (ref "LED2") (pin "5") (pinfunction "G_5") (pintype "unspecified"))
      (node (ref "U11") (pin "8") (pinfunction "SEG7/KS7_8") (pintype "unspecified"))
    )
    (net (code "71") (name "Net-(Q2-B)") (class "Default")
      (node (ref "Q2") (pin "1") (pinfunction "B_1") (pintype "unspecified"))
      (node (ref "R62") (pin "2") (pinfunction "2_2") (pintype "unspecified"))
    )
    (net (code "72") (name "Net-(U2-Q7)") (class "Default")
      (node (ref "U2") (pin "9") (pinfunction "Q7_9") (pintype "unspecified"))
      (node (ref "U3") (pin "10") (pinfunction "DS_10") (pintype "unspecified"))
    )
    (net (code "73") (name "Net-(U4-Q7)") (class "Default")
      (node (ref "U4") (pin "9") (pinfunction "Q7_9") (pintype "unspecified"))
      (node (ref "U5") (pin "10") (pinfunction "DS_10") (pintype "unspecified"))
    )
    (net (code "74") (name "Net-(U5-Q7)") (class "Default")
      (node (ref "U5") (pin "9") (pinfunction "Q7_9") (pintype "unspecified"))
      (node (ref "U6") (pin "10") (pinfunction "DS_10") (pintype "unspecified"))
    )
    (net (code "75") (name "Net-(U6-Q7)") (class "Default")
      (node (ref "U6") (pin "9") (pinfunction "Q7_9") (pintype "unspecified"))
      (node (ref "U7") (pin "10") (pinfunction "DS_10") (pintype "unspecified"))
    )
    (net (code "76") (name "Net-(U10-CC1)") (class "Default")
      (node (ref "R_CC1") (pin "2") (pinfunction "2_2") (pintype "input"))
      (node (ref "U10") (pin "A5") (pinfunction "CC1_A5") (pintype "unspecified"))
    )
    (net (code "77") (name "Net-(U10-CC2)") (class "Default")
      (node (ref "R_CC2") (pin "2") (pinfunction "2_2") (pintype "input"))
      (node (ref "U10") (pin "B5") (pinfunction "CC2_B5") (pintype "unspecified"))
    )
    (net (code "78") (name "Net-(U12-DS)") (class "Default")
      (node (ref "U12") (pin "10") (pinfunction "DS_10") (pintype "unspecified"))
      (node (ref "U3") (pin "9") (pinfunction "Q7_9") (pintype "unspecified"))
    )
    (net (code "79") (name "Net-(U12-Q7)") (class "Default")
      (node (ref "U12") (pin "9") (pinfunction "Q7_9") (pintype "unspecified"))
      (node (ref "U4") (pin "10") (pinfunction "DS_10") (pintype "unspecified"))
    )
    (net (code "80") (name "PA0") (class "Default")
      (node (ref "U1") (pin "11") (pinfunction "PA0_11") (pintype "unspecified"))
      (node (ref "U12") (pin "1") (pinfunction "PL#_1") (pintype "unspecified"))
      (node (ref "U2") (pin "1") (pinfunction "PL#_1") (pintype "unspecified"))
      (node (ref "U3") (pin "1") (pinfunction "PL#_1") (pintype "unspecified"))
      (node (ref "U4") (pin "1") (pinfunction "PL#_1") (pintype "unspecified"))
      (node (ref "U5") (pin "1") (pinfunction "PL#_1") (pintype "unspecified"))
      (node (ref "U6") (pin "1") (pinfunction "PL#_1") (pintype "unspecified"))
      (node (ref "U7") (pin "1") (pinfunction "PL#_1") (pintype "unspecified"))
    )
    (net (code "81") (name "PA1") (class "Default")
      (node (ref "U1") (pin "12") (pinfunction "PA1_12") (pintype "unspecified"))
      (node (ref "U12") (pin "2") (pinfunction "CP_2") (pintype "unspecified"))
      (node (ref "U2") (pin "2") (pinfunction "CP_2") (pintype "unspecified"))
      (node (ref "U3") (pin "2") (pinfunction "CP_2") (pintype "unspecified"))
      (node (ref "U4") (pin "2") (pinfunction "CP_2") (pintype "unspecified"))
      (node (ref "U5") (pin "2") (pinfunction "CP_2") (pintype "unspecified"))
      (node (ref "U6") (pin "2") (pinfunction "CP_2") (pintype "unspecified"))
      (node (ref "U7") (pin "2") (pinfunction "CP_2") (pintype "unspecified"))
    )
    (net (code "82") (name "PA2") (class "Default")
      (node (ref "C16") (pin "1") (pinfunction "1_1") (pintype "unspecified"))
      (node (ref "R51") (pin "2") (pinfunction "2_2") (pintype "unspecified"))
      (node (ref "U1") (pin "13") (pinfunction "PA2_13") (pintype "unspecified"))
      (node (ref "U11") (pin "18") (pinfunction "CLK_18") (pintype "unspecified"))
    )
    (net (code "83") (name "PA3") (class "Default")
      (node (ref "C17") (pin "1") (pinfunction "1_1") (pintype "unspecified"))
      (node (ref "R52") (pin "2") (pinfunction "2_2") (pintype "unspecified"))
      (node (ref "U1") (pin "14") (pinfunction "PA3_14") (pintype "unspecified"))
      (node (ref "U11") (pin "17") (pinfunction "DIO_17") (pintype "unspecified"))
    )
    (net (code "84") (name "PA4") (class "Default")
      (node (ref "R61") (pin "1") (pinfunction "1_1") (pintype "unspecified"))
      (node (ref "R62") (pin "1") (pinfunction "1_1") (pintype "unspecified"))
      (node (ref "U1") (pin "15") (pinfunction "PA4_15") (pintype "unspecified"))
    )
    (net (code "85") (name "PA6") (class "Default")
      (node (ref "U1") (pin "17") (pinfunction "PA6_17") (pintype "unspecified"))
      (node (ref "U7") (pin "9") (pinfunction "Q7_9") (pintype "unspecified"))
    )
    (net (code "86") (name "SWCLK") (class "Default")
      (node (ref "CN2") (pin "3") (pinfunction "3_3") (pintype "unspecified"))
      (node (ref "R2") (pin "2") (pinfunction "2_2") (pintype "unspecified"))
      (node (ref "U1") (pin "36") (pinfunction "PA14-BOOT0_36") (pintype "unspecified"))
    )
    (net (code "87") (name "SWDIO") (class "Default")
      (node (ref "CN2") (pin "2") (pinfunction "2_2") (pintype "unspecified"))
      (node (ref "U1") (pin "35") (pinfunction "PA13_35") (pintype "unspecified"))
    )
    (net (code "88") (name "TEST_GND") (class "Default")
      (node (ref "C1") (pin "1") (pinfunction "1_1") (pintype "unspecified"))
      (node (ref "C10") (pin "2") (pinfunction "2_2") (pintype "unspecified"))
      (node (ref "C11") (pin "2") (pinfunction "2_2") (pintype "unspecified"))
      (node (ref "C12") (pin "2") (pinfunction "2_2") (pintype "unspecified"))
      (node (ref "C13") (pin "2") (pinfunction "2_2") (pintype "input"))
      (node (ref "C14") (pin "2") (pinfunction "2_2") (pintype "unspecified"))
      (node (ref "C15") (pin "1") (pinfunction "1_1") (pintype "unspecified"))
      (node (ref "C16") (pin "2") (pinfunction "2_2") (pintype "unspecified"))
      (node (ref "C17") (pin "2") (pinfunction "2_2") (pintype "unspecified"))
      (node (ref "C2") (pin "1") (pinfunction "1_1") (pintype "unspecified"))
      (node (ref "C3") (pin "1") (pinfunction "1_1") (pintype "unspecified"))
      (node (ref "C4") (pin "1") (pinfunction "1_1") (pintype "unspecified"))
      (node (ref "C5") (pin "2") (pinfunction "2_2") (pintype "unspecified"))
      (node (ref "C6") (pin "1") (pinfunction "1_1") (pintype "unspecified"))
      (node (ref "C7") (pin "2") (pinfunction "2_2") (pintype "unspecified"))
      (node (ref "C8") (pin "2") (pinfunction "2_2") (pintype "unspecified"))
      (node (ref "C9") (pin "2") (pinfunction "2_2") (pintype "unspecified"))
      (node (ref "CN2") (pin "4") (pinfunction "GND_4") (pintype "unspecified"))
      (node (ref "CN3") (pin "1") (pinfunction "1_1") (pintype "unspecified"))
      (node (ref "CN3") (pin "2") (pinfunction "2_2") (pintype "unspecified"))
      (node (ref "CN3") (pin "3") (pinfunction "3_3") (pintype "unspecified"))
      (node (ref "CN3") (pin "4") (pinfunction "4_4") (pintype "unspecified"))
      (node (ref "CN3") (pin "5") (pinfunction "5_5") (pintype "unspecified"))
      (node (ref "D1") (pin "2") (pinfunction "A_2") (pintype "unspecified"))
      (node (ref "Q2") (pin "2") (pinfunction "E_2") (pintype "unspecified"))
      (node (ref "R2") (pin "1") (pinfunction "1_1") (pintype "unspecified"))
      (node (ref "R61") (pin "2") (pinfunction "2_2") (pintype "unspecified"))
      (node (ref "R_CC1") (pin "1") (pinfunction "1_1") (pintype "input"))
      (node (ref "R_CC2") (pin "1") (pinfunction "1_1") (pintype "input"))
      (node (ref "SW1") (pin "3") (pinfunction "3_3") (pintype "unspecified"))
      (node (ref "U1") (pin "7") (pinfunction "VSS/VSSA_7") (pintype "unspecified"))
      (node (ref "U10") (pin "17") (pinfunction "EH_17") (pintype "unspecified"))
      (node (ref "U10") (pin "18") (pinfunction "EH_18") (pintype "unspecified"))
      (node (ref "U10") (pin "19") (pinfunction "EH_19") (pintype "unspecified"))
      (node (ref "U10") (pin "20") (pinfunction "EH_20") (pintype "unspecified"))
      (node (ref "U10") (pin "A12B1") (pinfunction "GND_A12B1") (pintype "unspecified"))
      (node (ref "U11") (pin "1") (pinfunction "GND_1") (pintype "unspecified"))
      (node (ref "U12") (pin "15") (pinfunction "CE#_15") (pintype "unspecified"))
      (node (ref "U12") (pin "8") (pinfunction "GND_8") (pintype "unspecified"))
      (node (ref "U2") (pin "15") (pinfunction "CE#_15") (pintype "unspecified"))
      (node (ref "U2") (pin "8") (pinfunction "GND_8") (pintype "unspecified"))
      (node (ref "U3") (pin "15") (pinfunction "CE#_15") (pintype "unspecified"))
      (node (ref "U3") (pin "8") (pinfunction "GND_8") (pintype "unspecified"))
      (node (ref "U4") (pin "15") (pinfunction "CE#_15") (pintype "unspecified"))
      (node (ref "U4") (pin "8") (pinfunction "GND_8") (pintype "unspecified"))
      (node (ref "U5") (pin "15") (pinfunction "CE#_15") (pintype "unspecified"))
      (node (ref "U5") (pin "8") (pinfunction "GND_8") (pintype "unspecified"))
      (node (ref "U6") (pin "15") (pinfunction "CE#_15") (pintype "unspecified"))
      (node (ref "U6") (pin "8") (pinfunction "GND_8") (pintype "unspecified"))
      (node (ref "U7") (pin "15") (pinfunction "CE#_15") (pintype "unspecified"))
      (node (ref "U7") (pin "8") (pinfunction "GND_8") (pintype "unspecified"))
      (node (ref "U9") (pin "2") (pinfunction "GND_2") (pintype "unspecified"))
    )
    (net (code "89") (name "VCC") (class "Default")
      (node (ref "BUZZER1") (pin "1") (pinfunction "+_1") (pintype "unspecified"))
      (node (ref "C10") (pin "1") (pinfunction "1_1") (pintype "unspecified"))
      (node (ref "C11") (pin "1") (pinfunction "1_1") (pintype "unspecified"))
      (node (ref "C12") (pin "1") (pinfunction "1_1") (pintype "unspecified"))
      (node (ref "C13") (pin "1") (pinfunction "1_1") (pintype "input"))
      (node (ref "C14") (pin "1") (pinfunction "1_1") (pintype "unspecified"))
      (node (ref "C15") (pin "2") (pinfunction "2_2") (pintype "unspecified"))
      (node (ref "C2") (pin "2") (pinfunction "2_2") (pintype "unspecified"))
      (node (ref "C3") (pin "2") (pinfunction "2_2") (pintype "unspecified"))
      (node (ref "C4") (pin "2") (pinfunction "2_2") (pintype "unspecified"))
      (node (ref "C5") (pin "1") (pinfunction "1_1") (pintype "unspecified"))
      (node (ref "C7") (pin "1") (pinfunction "1_1") (pintype "unspecified"))
      (node (ref "C8") (pin "1") (pinfunction "1_1") (pintype "unspecified"))
      (node (ref "C9") (pin "1") (pinfunction "1_1") (pintype "unspecified"))
      (node (ref "CN2") (pin "1") (pinfunction "VCC_1") (pintype "unspecified"))
      (node (ref "R1") (pin "2") (pinfunction "2_2") (pintype "unspecified"))
      (node (ref "R10") (pin "2") (pinfunction "2_2") (pintype "unspecified"))
      (node (ref "R11") (pin "2") (pinfunction "2_2") (pintype "unspecified"))
      (node (ref "R12") (pin "2") (pinfunction "2_2") (pintype "unspecified"))
      (node (ref "R13") (pin "2") (pinfunction "2_2") (pintype "unspecified"))
      (node (ref "R14") (pin "2") (pinfunction "2_2") (pintype "unspecified"))
      (node (ref "R15") (pin "2") (pinfunction "2_2") (pintype "unspecified"))
      (node (ref "R16") (pin "2") (pinfunction "2_2") (pintype "unspecified"))
      (node (ref "R17") (pin "2") (pinfunction "2_2") (pintype "unspecified"))
      (node (ref "R18") (pin "2") (pinfunction "2_2") (pintype "unspecified"))
      (node (ref "R19") (pin "2") (pinfunction "2_2") (pintype "unspecified"))
      (node (ref "R20") (pin "2") (pinfunction "2_2") (pintype "unspecified"))
      (node (ref "R21") (pin "2") (pinfunction "2_2") (pintype "unspecified"))
      (node (ref "R22") (pin "2") (pinfunction "2_2") (pintype "unspecified"))
      (node (ref "R23") (pin "2") (pinfunction "2_2") (pintype "unspecified"))
      (node (ref "R24") (pin "2") (pinfunction "2_2") (pintype "unspecified"))
      (node (ref "R25") (pin "2") (pinfunction "2_2") (pintype "unspecified"))
      (node (ref "R26") (pin "2") (pinfunction "2_2") (pintype "unspecified"))
      (node (ref "R27") (pin "2") (pinfunction "2_2") (pintype "unspecified"))
      (node (ref "R28") (pin "2") (pinfunction "2_2") (pintype "unspecified"))
      (node (ref "R29") (pin "2") (pinfunction "2_2") (pintype "unspecified"))
      (node (ref "R3") (pin "2") (pinfunction "2_2") (pintype "unspecified"))
      (node (ref "R30") (pin "2") (pinfunction "2_2") (pintype "unspecified"))
      (node (ref "R31") (pin "2") (pinfunction "2_2") (pintype "unspecified"))
      (node (ref "R32") (pin "2") (pinfunction "2_2") (pintype "unspecified"))
      (node (ref "R33") (pin "2") (pinfunction "2_2") (pintype "unspecified"))
      (node (ref "R34") (pin "2") (pinfunction "2_2") (pintype "unspecified"))
      (node (ref "R35") (pin "2") (pinfunction "2_2") (pintype "unspecified"))
      (node (ref "R36") (pin "2") (pinfunction "2_2") (pintype "unspecified"))
      (node (ref "R37") (pin "2") (pinfunction "2_2") (pintype "unspecified"))
      (node (ref "R38") (pin "2") (pinfunction "2_2") (pintype "unspecified"))
      (node (ref "R39") (pin "2") (pinfunction "2_2") (pintype "unspecified"))
      (node (ref "R4") (pin "2") (pinfunction "2_2") (pintype "unspecified"))
      (node (ref "R40") (pin "2") (pinfunction "2_2") (pintype "unspecified"))
      (node (ref "R41") (pin "2") (pinfunction "2_2") (pintype "unspecified"))
      (node (ref "R42") (pin "2") (pinfunction "2_2") (pintype "unspecified"))
      (node (ref "R43") (pin "2") (pinfunction "2_2") (pintype "unspecified"))
      (node (ref "R44") (pin "2") (pinfunction "2_2") (pintype "unspecified"))
      (node (ref "R45") (pin "2") (pinfunction "2_2") (pintype "unspecified"))
      (node (ref "R46") (pin "2") (pinfunction "2_2") (pintype "unspecified"))
      (node (ref "R47") (pin "2") (pinfunction "2_2") (pintype "unspecified"))
      (node (ref "R48") (pin "2") (pinfunction "2_2") (pintype "unspecified"))
      (node (ref "R49") (pin "2") (pinfunction "2_2") (pintype "unspecified"))
      (node (ref "R5") (pin "2") (pinfunction "2_2") (pintype "unspecified"))
      (node (ref "R50") (pin "2") (pinfunction "2_2") (pintype "unspecified"))
      (node (ref "R51") (pin "1") (pinfunction "1_1") (pintype "unspecified"))
      (node (ref "R52") (pin "1") (pinfunction "1_1") (pintype "unspecified"))
      (node (ref "R53") (pin "2") (pinfunction "2_2") (pintype "unspecified"))
      (node (ref "R54") (pin "2") (pinfunction "2_2") (pintype "unspecified"))
      (node (ref "R55") (pin "2") (pinfunction "2_2") (pintype "unspecified"))
      (node (ref "R56") (pin "2") (pinfunction "2_2") (pintype "unspecified"))
      (node (ref "R57") (pin "2") (pinfunction "2_2") (pintype "unspecified"))
      (node (ref "R58") (pin "2") (pinfunction "2_2") (pintype "unspecified"))
      (node (ref "R59") (pin "2") (pinfunction "2_2") (pintype "unspecified"))
      (node (ref "R6") (pin "2") (pinfunction "2_2") (pintype "unspecified"))
      (node (ref "R60") (pin "2") (pinfunction "2_2") (pintype "unspecified"))
      (node (ref "R7") (pin "2") (pinfunction "2_2") (pintype "unspecified"))
      (node (ref "R8") (pin "2") (pinfunction "2_2") (pintype "unspecified"))
      (node (ref "R9") (pin "2") (pinfunction "2_2") (pintype "unspecified"))
      (node (ref "U1") (pin "5") (pinfunction "VREF+_5") (pintype "unspecified"))
      (node (ref "U1") (pin "6") (pinfunction "VDD/VDDA_6") (pintype "unspecified"))
      (node (ref "U11") (pin "16") (pinfunction "VDD_16") (pintype "unspecified"))
      (node (ref "U12") (pin "16") (pinfunction "VCC_16") (pintype "unspecified"))
      (node (ref "U2") (pin "10") (pinfunction "DS_10") (pintype "unspecified"))
      (node (ref "U2") (pin "16") (pinfunction "VCC_16") (pintype "unspecified"))
      (node (ref "U3") (pin "16") (pinfunction "VCC_16") (pintype "unspecified"))
      (node (ref "U4") (pin "16") (pinfunction "VCC_16") (pintype "unspecified"))
      (node (ref "U5") (pin "16") (pinfunction "VCC_16") (pintype "unspecified"))
      (node (ref "U6") (pin "16") (pinfunction "VCC_16") (pintype "unspecified"))
      (node (ref "U7") (pin "16") (pinfunction "VCC_16") (pintype "unspecified"))
      (node (ref "U9") (pin "5") (pinfunction "VOUT_5") (pintype "unspecified"))
    )
    (net (code "90") (name "unconnected-(SW1-Pad2)") (class "Default")
      (node (ref "SW1") (pin "2") (pinfunction "2_2") (pintype "unspecified"))
    )
    (net (code "91") (name "unconnected-(SW1-Pad4)") (class "Default")
      (node (ref "SW1") (pin "4") (pinfunction "4_4") (pintype "unspecified"))
    )
    (net (code "92") (name "unconnected-(U1-PA5-Pad16)") (class "Default")
      (node (ref "U1") (pin "16") (pinfunction "PA5_16") (pintype "unspecified"))
    )
    (net (code "93") (name "unconnected-(U1-PA7-Pad18)") (class "Default")
      (node (ref "U1") (pin "18") (pinfunction "PA7_18") (pintype "unspecified"))
    )
    (net (code "94") (name "unconnected-(U1-PA8-Pad28)") (class "Default")
      (node (ref "U1") (pin "28") (pinfunction "PA8_28") (pintype "unspecified"))
    )
    (net (code "95") (name "unconnected-(U1-PA9-Pad29)") (class "Default")
      (node (ref "U1") (pin "29") (pinfunction "PA9_29") (pintype "unspecified"))
    )
    (net (code "96") (name "unconnected-(U1-PA10-Pad32)") (class "Default")
      (node (ref "U1") (pin "32") (pinfunction "PA10_32") (pintype "unspecified"))
    )
    (net (code "97") (name "unconnected-(U1-PA11[PA9]-Pad33)") (class "Default")
      (node (ref "U1") (pin "33") (pinfunction "PA11[PA9]_33") (pintype "unspecified"))
    )
    (net (code "98") (name "unconnected-(U1-PA12[PA10]-Pad34)") (class "Default")
      (node (ref "U1") (pin "34") (pinfunction "PA12[PA10]_34") (pintype "unspecified"))
    )
    (net (code "99") (name "unconnected-(U1-PA15-Pad37)") (class "Default")
      (node (ref "U1") (pin "37") (pinfunction "PA15_37") (pintype "unspecified"))
    )
    (net (code "100") (name "unconnected-(U1-PB0-Pad19)") (class "Default")
      (node (ref "U1") (pin "19") (pinfunction "PB0_19") (pintype "unspecified"))
    )
    (net (code "101") (name "unconnected-(U1-PB1-Pad20)") (class "Default")
      (node (ref "U1") (pin "20") (pinfunction "PB1_20") (pintype "unspecified"))
    )
    (net (code "102") (name "unconnected-(U1-PB2-Pad21)") (class "Default")
      (node (ref "U1") (pin "21") (pinfunction "PB2_21") (pintype "unspecified"))
    )
    (net (code "103") (name "unconnected-(U1-PB3-Pad42)") (class "Default")
      (node (ref "U1") (pin "42") (pinfunction "PB3_42") (pintype "unspecified"))
    )
    (net (code "104") (name "unconnected-(U1-PB4-Pad43)") (class "Default")
      (node (ref "U1") (pin "43") (pinfunction "PB4_43") (pintype "unspecified"))
    )
    (net (code "105") (name "unconnected-(U1-PB5-Pad44)") (class "Default")
      (node (ref "U1") (pin "44") (pinfunction "PB5_44") (pintype "unspecified"))
    )
    (net (code "106") (name "unconnected-(U1-PB6-Pad45)") (class "Default")
      (node (ref "U1") (pin "45") (pinfunction "PB6_45") (pintype "unspecified"))
    )
    (net (code "107") (name "unconnected-(U1-PB7-Pad46)") (class "Default")
      (node (ref "U1") (pin "46") (pinfunction "PB7_46") (pintype "unspecified"))
    )
    (net (code "108") (name "unconnected-(U1-PB8-Pad47)") (class "Default")
      (node (ref "U1") (pin "47") (pinfunction "PB8_47") (pintype "unspecified"))
    )
    (net (code "109") (name "unconnected-(U1-PB9-Pad48)") (class "Default")
      (node (ref "U1") (pin "48") (pinfunction "PB9_48") (pintype "unspecified"))
    )
    (net (code "110") (name "unconnected-(U1-PB10-Pad22)") (class "Default")
      (node (ref "U1") (pin "22") (pinfunction "PB10_22") (pintype "unspecified"))
    )
    (net (code "111") (name "unconnected-(U1-PB11-Pad23)") (class "Default")
      (node (ref "U1") (pin "23") (pinfunction "PB11_23") (pintype "unspecified"))
    )
    (net (code "112") (name "unconnected-(U1-PB12-Pad24)") (class "Default")
      (node (ref "U1") (pin "24") (pinfunction "PB12_24") (pintype "unspecified"))
    )
    (net (code "113") (name "unconnected-(U1-PB13-Pad25)") (class "Default")
      (node (ref "U1") (pin "25") (pinfunction "PB13_25") (pintype "unspecified"))
    )
    (net (code "114") (name "unconnected-(U1-PB14-Pad26)") (class "Default")
      (node (ref "U1") (pin "26") (pinfunction "PB14_26") (pintype "unspecified"))
    )
    (net (code "115") (name "unconnected-(U1-PB15-Pad27)") (class "Default")
      (node (ref "U1") (pin "27") (pinfunction "PB15_27") (pintype "unspecified"))
    )
    (net (code "116") (name "unconnected-(U1-PC6-Pad30)") (class "Default")
      (node (ref "U1") (pin "30") (pinfunction "PC6_30") (pintype "unspecified"))
    )
    (net (code "117") (name "unconnected-(U1-PC7-Pad31)") (class "Default")
      (node (ref "U1") (pin "31") (pinfunction "PC7_31") (pintype "unspecified"))
    )
    (net (code "118") (name "unconnected-(U1-PC13-Pad1)") (class "Default")
      (node (ref "U1") (pin "1") (pinfunction "PC13_1") (pintype "unspecified"))
    )
    (net (code "119") (name "unconnected-(U1-PC14-OSCX_IN-Pad2)") (class "Default")
      (node (ref "U1") (pin "2") (pinfunction "PC14-OSCX_IN_2") (pintype "unspecified"))
    )
    (net (code "120") (name "unconnected-(U1-PC15-OSCX_OUT-Pad3)") (class "Default")
      (node (ref "U1") (pin "3") (pinfunction "PC15-OSCX_OUT_3") (pintype "unspecified"))
    )
    (net (code "121") (name "unconnected-(U1-PD0-Pad38)") (class "Default")
      (node (ref "U1") (pin "38") (pinfunction "PD0_38") (pintype "unspecified"))
    )
    (net (code "122") (name "unconnected-(U1-PD1-Pad39)") (class "Default")
      (node (ref "U1") (pin "39") (pinfunction "PD1_39") (pintype "unspecified"))
    )
    (net (code "123") (name "unconnected-(U1-PD2-Pad40)") (class "Default")
      (node (ref "U1") (pin "40") (pinfunction "PD2_40") (pintype "unspecified"))
    )
    (net (code "124") (name "unconnected-(U1-PD3-Pad41)") (class "Default")
      (node (ref "U1") (pin "41") (pinfunction "PD3_41") (pintype "unspecified"))
    )
    (net (code "125") (name "unconnected-(U1-PF0-OSC_IN-Pad8)") (class "Default")
      (node (ref "U1") (pin "8") (pinfunction "PF0-OSC_IN_8") (pintype "unspecified"))
    )
    (net (code "126") (name "unconnected-(U1-PF1-OSC_OUT-Pad9)") (class "Default")
      (node (ref "U1") (pin "9") (pinfunction "PF1-OSC_OUT_9") (pintype "unspecified"))
    )
    (net (code "127") (name "unconnected-(U1-PF3-Pad4)") (class "Default")
      (node (ref "U1") (pin "4") (pinfunction "PF3_4") (pintype "unspecified"))
    )
    (net (code "128") (name "unconnected-(U2-Q7#-Pad7)") (class "Default")
      (node (ref "U2") (pin "7") (pinfunction "Q7#_7") (pintype "unspecified"))
    )
    (net (code "129") (name "unconnected-(U3-Q7#-Pad7)") (class "Default")
      (node (ref "U3") (pin "7") (pinfunction "Q7#_7") (pintype "unspecified"))
    )
    (net (code "130") (name "unconnected-(U4-Q7#-Pad7)") (class "Default")
      (node (ref "U4") (pin "7") (pinfunction "Q7#_7") (pintype "unspecified"))
    )
    (net (code "131") (name "unconnected-(U5-Q7#-Pad7)") (class "Default")
      (node (ref "U5") (pin "7") (pinfunction "Q7#_7") (pintype "unspecified"))
    )
    (net (code "132") (name "unconnected-(U6-Q7#-Pad7)") (class "Default")
      (node (ref "U6") (pin "7") (pinfunction "Q7#_7") (pintype "unspecified"))
    )
    (net (code "133") (name "unconnected-(U7-Q7#-Pad7)") (class "Default")
      (node (ref "U7") (pin "7") (pinfunction "Q7#_7") (pintype "unspecified"))
    )
    (net (code "134") (name "unconnected-(U9-NC-Pad4)") (class "Default")
      (node (ref "U9") (pin "4") (pinfunction "NC_4") (pintype "unspecified"))
    )
    (net (code "135") (name "unconnected-(U10-D+-PadA6)") (class "Default")
      (node (ref "U10") (pin "A6") (pinfunction "D+_A6") (pintype "unspecified"))
    )
    (net (code "136") (name "unconnected-(U10-D+-PadB6)") (class "Default")
      (node (ref "U10") (pin "B6") (pinfunction "D+_B6") (pintype "unspecified"))
    )
    (net (code "137") (name "unconnected-(U10-D--PadA7)") (class "Default")
      (node (ref "U10") (pin "A7") (pinfunction "D-_A7") (pintype "unspecified"))
    )
    (net (code "138") (name "unconnected-(U10-D--PadB7)") (class "Default")
      (node (ref "U10") (pin "B7") (pinfunction "D-_B7") (pintype "unspecified"))
    )
    (net (code "139") (name "unconnected-(U10-GND-PadB12A1)") (class "Default")
      (node (ref "U10") (pin "B12A1") (pinfunction "GND_B12A1") (pintype "unspecified"))
    )
    (net (code "140") (name "unconnected-(U10-SBU1-PadA8)") (class "Default")
      (node (ref "U10") (pin "A8") (pinfunction "SBU1_A8") (pintype "unspecified"))
    )
    (net (code "141") (name "unconnected-(U10-SBU2-PadB8)") (class "Default")
      (node (ref "U10") (pin "B8") (pinfunction "SBU2_B8") (pintype "unspecified"))
    )
    (net (code "142") (name "unconnected-(U11-GRID3-Pad13)") (class "Default")
      (node (ref "U11") (pin "13") (pinfunction "GRID3_13") (pintype "unspecified"))
    )
    (net (code "143") (name "unconnected-(U11-GRID4-Pad12)") (class "Default")
      (node (ref "U11") (pin "12") (pinfunction "GRID4_12") (pintype "unspecified"))
    )
    (net (code "144") (name "unconnected-(U11-GRID5-Pad11)") (class "Default")
      (node (ref "U11") (pin "11") (pinfunction "GRID5_11") (pintype "unspecified"))
    )
    (net (code "145") (name "unconnected-(U11-GRID6-Pad10)") (class "Default")
      (node (ref "U11") (pin "10") (pinfunction "GRID6_10") (pintype "unspecified"))
    )
    (net (code "146") (name "unconnected-(U11-K1-Pad19)") (class "Default")
      (node (ref "U11") (pin "19") (pinfunction "K1_19") (pintype "unspecified"))
    )
    (net (code "147") (name "unconnected-(U11-K2-Pad20)") (class "Default")
      (node (ref "U11") (pin "20") (pinfunction "K2_20") (pintype "unspecified"))
    )
    (net (code "148") (name "unconnected-(U12-Q7#-Pad7)") (class "Default")
      (node (ref "U12") (pin "7") (pinfunction "Q7#_7") (pintype "unspecified"))
    )
  )
)
